# Totoro.net
KiCad netlist of a schematic drawn in EAGLE
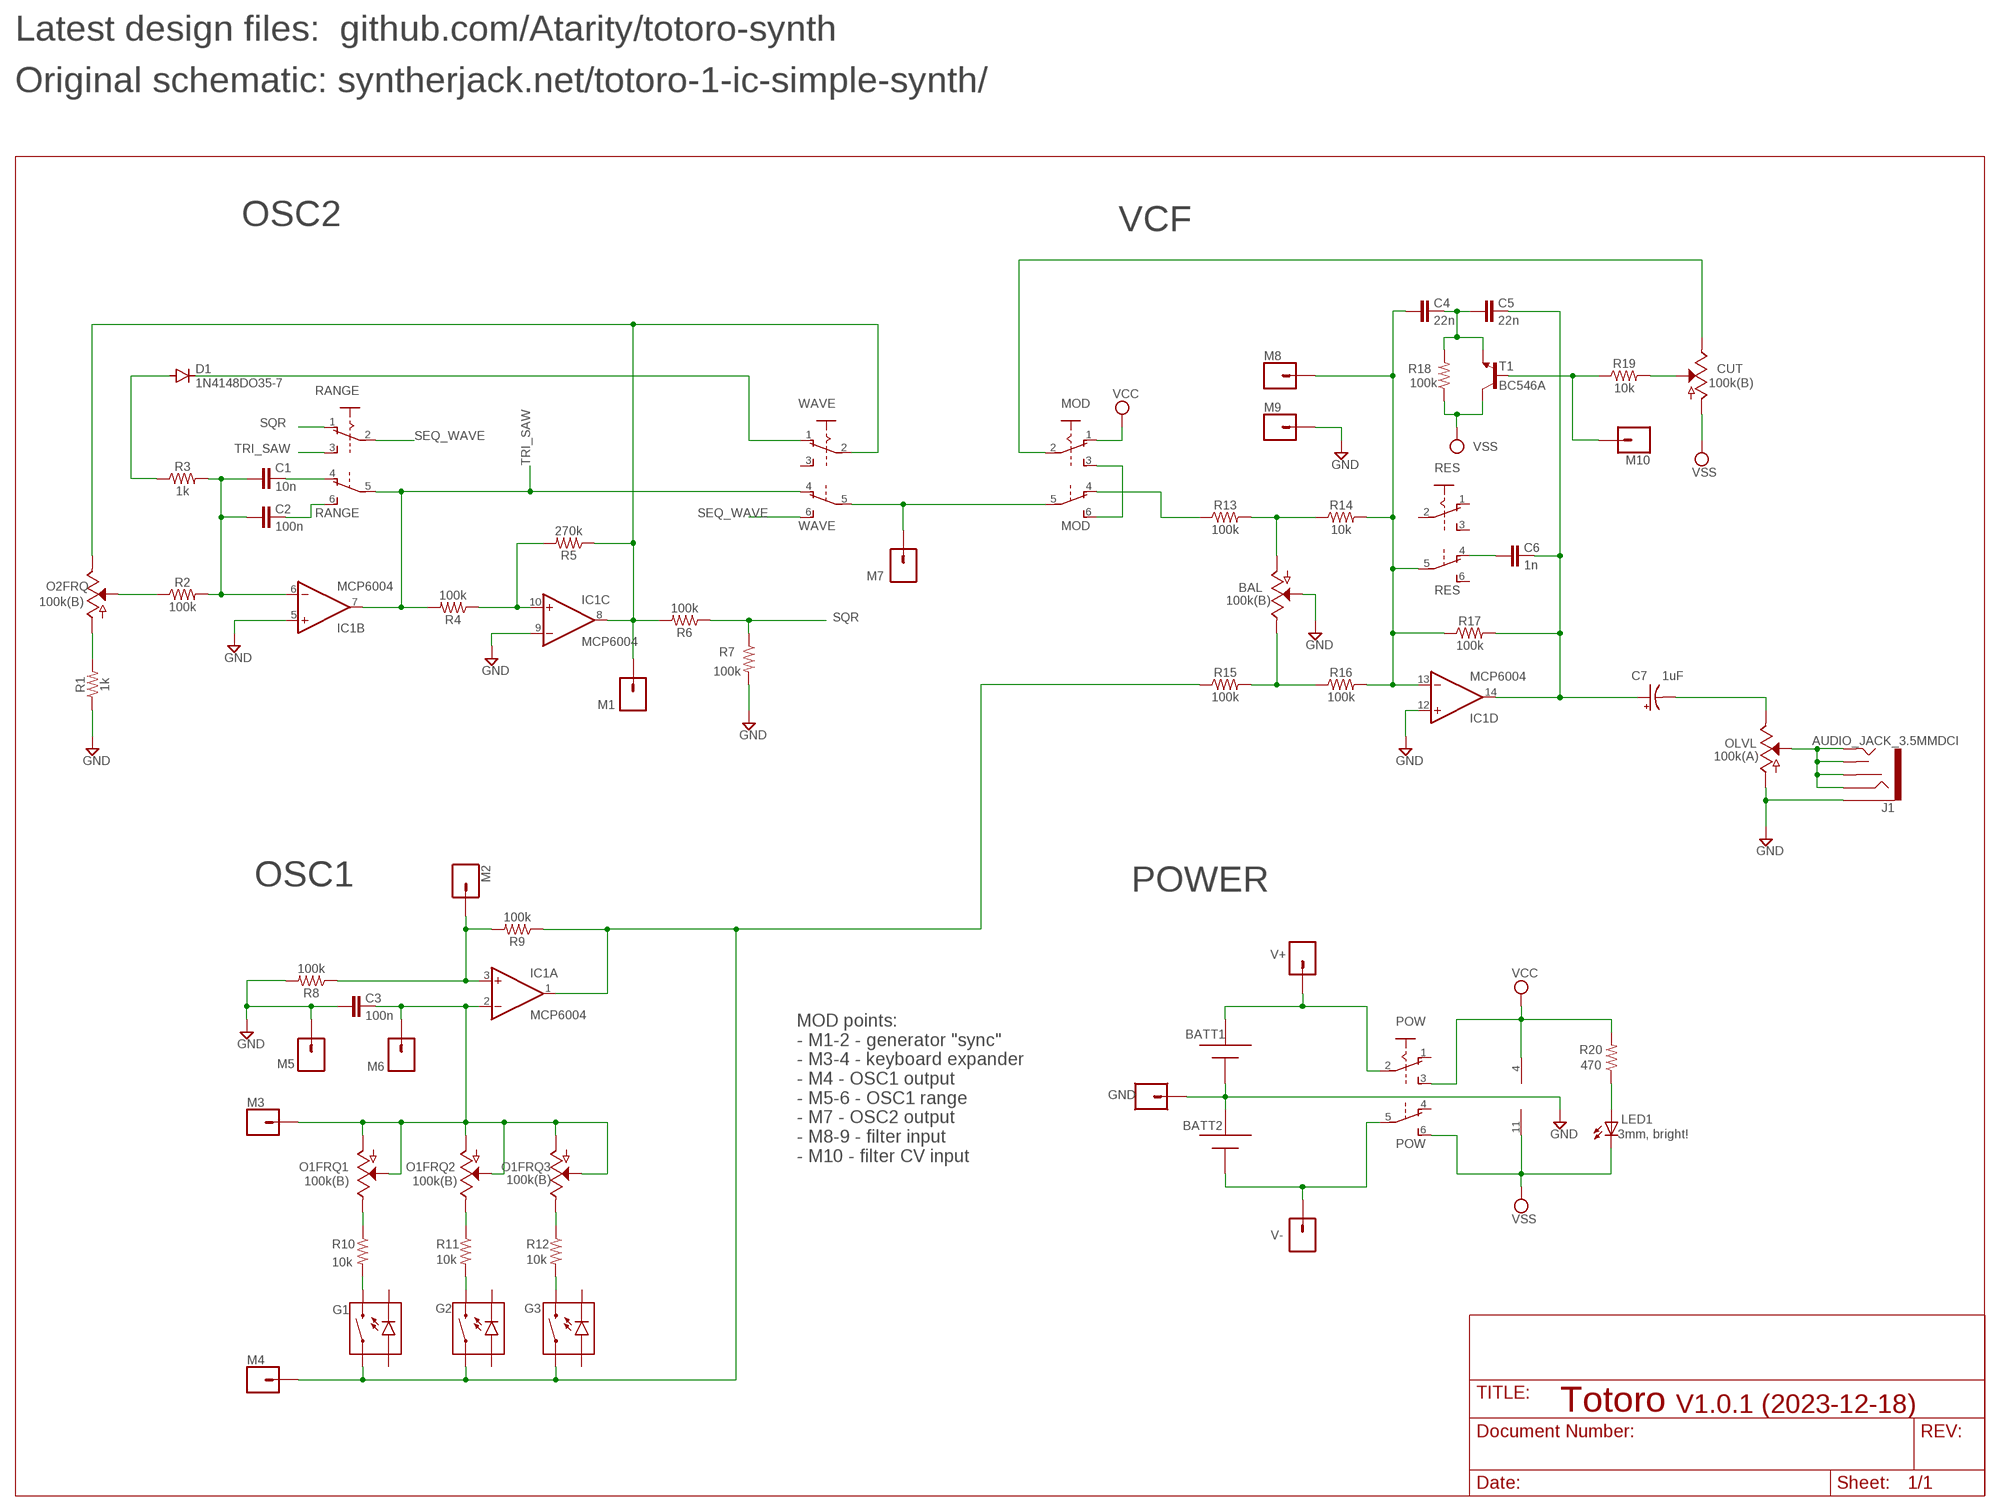
[diagram p0: schematic, sheet 1]

(export (version "E")
  (design (tool "Eeschema 10.0.6"))
  (components
    (comp (ref "BAL")
      (value "100k(B)")
      (footprint "eagle-import:POT-PTH-ALPS-KIT")
      (libsource (lib "eagle-import") (part "POTENTIOMETER-GATE-SWAPPED"))
    )
    (comp (ref "BATT1")
      (value "ATARITY-AAAKLS5-817D")
      (footprint "eagle-import:KLS5-817-D")
      (libsource (lib "eagle-import") (part "ATARITY-AAAKLS5-817D"))
    )
    (comp (ref "BATT2")
      (value "ATARITY-AAAKLS5-817D")
      (footprint "eagle-import:KLS5-817-D")
      (libsource (lib "eagle-import") (part "ATARITY-AAAKLS5-817D"))
    )
    (comp (ref "C1")
      (value "10n")
      (footprint "eagle-import:C050-024X044")
      (libsource (lib "eagle-import") (part "C-EU050-024X044"))
    )
    (comp (ref "C2")
      (value "100n")
      (footprint "eagle-import:C050-024X044")
      (libsource (lib "eagle-import") (part "C-EU050-024X044"))
    )
    (comp (ref "C3")
      (value "100n")
      (footprint "eagle-import:C050-024X044")
      (libsource (lib "eagle-import") (part "C-EU050-024X044"))
    )
    (comp (ref "C4")
      (value "22n")
      (footprint "eagle-import:C050-024X044")
      (libsource (lib "eagle-import") (part "C-EU050-024X044"))
    )
    (comp (ref "C5")
      (value "22n")
      (footprint "eagle-import:C050-024X044")
      (libsource (lib "eagle-import") (part "C-EU050-024X044"))
    )
    (comp (ref "C6")
      (value "1n")
      (footprint "eagle-import:C050-024X044")
      (libsource (lib "eagle-import") (part "C-EU050-024X044"))
    )
    (comp (ref "C7")
      (value "1uF")
      (footprint "eagle-import:CPOL-RADIAL-2.5MM-5MM")
      (libsource (lib "eagle-import") (part "10UF-POLAR-RADIAL-2.5MM-25V-20%"))
    )
    (comp (ref "CUT")
      (value "100k(B)")
      (footprint "eagle-import:POT-PTH-ALPS-KIT")
      (libsource (lib "eagle-import") (part "POTENTIOMETER-GATE-SWAPPED"))
    )
    (comp (ref "D1")
      (value "1N4148DO35-7")
      (footprint "eagle-import:DO35-7")
      (libsource (lib "eagle-import") (part "1N4148DO35-7"))
    )
    (comp (ref "G1")
      (value "MECHANICAL-KEYBOARD1U")
      (footprint "eagle-import:CHERRY-MX-LED-1U")
      (libsource (lib "eagle-import") (part "MECHANICAL-KEYBOARD1U"))
    )
    (comp (ref "G2")
      (value "MECHANICAL-KEYBOARD1U")
      (footprint "eagle-import:CHERRY-MX-LED-1U")
      (libsource (lib "eagle-import") (part "MECHANICAL-KEYBOARD1U"))
    )
    (comp (ref "G3")
      (value "MECHANICAL-KEYBOARD1U")
      (footprint "eagle-import:CHERRY-MX-LED-1U")
      (libsource (lib "eagle-import") (part "MECHANICAL-KEYBOARD1U"))
    )
    (comp (ref "GND")
      (value "CONN_01")
      (footprint "eagle-import:1X01")
      (libsource (lib "eagle-import") (part "CONN_01"))
    )
    (comp (ref "IC1")
      (value "MCP6004")
      (footprint "eagle-import:DIL14")
      (libsource (lib "eagle-import") (part "4AMP_P4+11N"))
    )
    (comp (ref "J1")
      (value "AUDIO_JACK_3.5MMDCI")
      (footprint "eagle-import:DCI-ST-033")
      (libsource (lib "eagle-import") (part "AUDIO_JACK_3.5MMDCI"))
    )
    (comp (ref "LED1")
      (value "3mm, bright!")
      (footprint "eagle-import:LED3MM")
      (libsource (lib "eagle-import") (part "LED3MM"))
    )
    (comp (ref "M1")
      (value "CONN_01")
      (footprint "eagle-import:1X01")
      (libsource (lib "eagle-import") (part "CONN_01"))
    )
    (comp (ref "M2")
      (value "CONN_01")
      (footprint "eagle-import:1X01")
      (libsource (lib "eagle-import") (part "CONN_01"))
    )
    (comp (ref "M3")
      (value "CONN_01")
      (footprint "eagle-import:1X01")
      (libsource (lib "eagle-import") (part "CONN_01"))
    )
    (comp (ref "M4")
      (value "CONN_01")
      (footprint "eagle-import:1X01")
      (libsource (lib "eagle-import") (part "CONN_01"))
    )
    (comp (ref "M5")
      (value "CONN_01")
      (footprint "eagle-import:1X01")
      (libsource (lib "eagle-import") (part "CONN_01"))
    )
    (comp (ref "M6")
      (value "CONN_01")
      (footprint "eagle-import:1X01")
      (libsource (lib "eagle-import") (part "CONN_01"))
    )
    (comp (ref "M7")
      (value "CONN_01")
      (footprint "eagle-import:1X01")
      (libsource (lib "eagle-import") (part "CONN_01"))
    )
    (comp (ref "M8")
      (value "CONN_01")
      (footprint "eagle-import:1X01")
      (libsource (lib "eagle-import") (part "CONN_01"))
    )
    (comp (ref "M9")
      (value "CONN_01")
      (footprint "eagle-import:1X01")
      (libsource (lib "eagle-import") (part "CONN_01"))
    )
    (comp (ref "M10")
      (value "CONN_01")
      (footprint "eagle-import:1X01")
      (libsource (lib "eagle-import") (part "CONN_01"))
    )
    (comp (ref "MOD")
      (value "PB22E07")
      (footprint "eagle-import:PB22E07")
      (libsource (lib "eagle-import") (part "PB22E07"))
    )
    (comp (ref "O1FRQ1")
      (value "100k(B)")
      (footprint "eagle-import:POT-PTH-ALPS-KIT")
      (libsource (lib "eagle-import") (part "POTENTIOMETER-GATE-SWAPPED"))
    )
    (comp (ref "O1FRQ2")
      (value "100k(B)")
      (footprint "eagle-import:POT-PTH-ALPS-KIT")
      (libsource (lib "eagle-import") (part "POTENTIOMETER-GATE-SWAPPED"))
    )
    (comp (ref "O1FRQ3")
      (value "100k(B)")
      (footprint "eagle-import:POT-PTH-ALPS-KIT")
      (libsource (lib "eagle-import") (part "POTENTIOMETER-GATE-SWAPPED"))
    )
    (comp (ref "O2FRQ")
      (value "100k(B)")
      (footprint "eagle-import:POT-PTH-ALPS-KIT")
      (libsource (lib "eagle-import") (part "POTENTIOMETER-GATE-SWAPPED"))
    )
    (comp (ref "OLVL")
      (value "100k(A)")
      (footprint "eagle-import:POT-PTH-ALPS-KIT")
      (libsource (lib "eagle-import") (part "POTENTIOMETER-GATE-SWAPPED"))
    )
    (comp (ref "POW")
      (value "PB22E07")
      (footprint "eagle-import:PB22E07")
      (libsource (lib "eagle-import") (part "PB22E07"))
    )
    (comp (ref "R1")
      (value "1k")
      (footprint "eagle-import:AXIAL-0.3")
      (libsource (lib "eagle-import") (part "RESISTORAXIAL-0.3"))
    )
    (comp (ref "R2")
      (value "100k")
      (footprint "eagle-import:AXIAL-0.3")
      (libsource (lib "eagle-import") (part "RESISTORAXIAL-0.3"))
    )
    (comp (ref "R3")
      (value "1k")
      (footprint "eagle-import:AXIAL-0.3")
      (libsource (lib "eagle-import") (part "RESISTORAXIAL-0.3"))
    )
    (comp (ref "R4")
      (value "100k")
      (footprint "eagle-import:AXIAL-0.3")
      (libsource (lib "eagle-import") (part "RESISTORAXIAL-0.3"))
    )
    (comp (ref "R5")
      (value "270k")
      (footprint "eagle-import:AXIAL-0.3")
      (libsource (lib "eagle-import") (part "RESISTORAXIAL-0.3"))
    )
    (comp (ref "R6")
      (value "100k")
      (footprint "eagle-import:AXIAL-0.3")
      (libsource (lib "eagle-import") (part "RESISTORAXIAL-0.3"))
    )
    (comp (ref "R7")
      (value "100k")
      (footprint "eagle-import:AXIAL-0.3")
      (libsource (lib "eagle-import") (part "RESISTORAXIAL-0.3"))
    )
    (comp (ref "R8")
      (value "100k")
      (footprint "eagle-import:AXIAL-0.3")
      (libsource (lib "eagle-import") (part "RESISTORAXIAL-0.3"))
    )
    (comp (ref "R9")
      (value "100k")
      (footprint "eagle-import:AXIAL-0.3")
      (libsource (lib "eagle-import") (part "RESISTORAXIAL-0.3"))
    )
    (comp (ref "R10")
      (value "10k")
      (footprint "eagle-import:AXIAL-0.3")
      (libsource (lib "eagle-import") (part "RESISTORAXIAL-0.3"))
    )
    (comp (ref "R11")
      (value "10k")
      (footprint "eagle-import:AXIAL-0.3")
      (libsource (lib "eagle-import") (part "RESISTORAXIAL-0.3"))
    )
    (comp (ref "R12")
      (value "10k")
      (footprint "eagle-import:AXIAL-0.3")
      (libsource (lib "eagle-import") (part "RESISTORAXIAL-0.3"))
    )
    (comp (ref "R13")
      (value "100k")
      (footprint "eagle-import:AXIAL-0.3")
      (libsource (lib "eagle-import") (part "RESISTORAXIAL-0.3"))
    )
    (comp (ref "R14")
      (value "10k")
      (footprint "eagle-import:AXIAL-0.3")
      (libsource (lib "eagle-import") (part "RESISTORAXIAL-0.3"))
    )
    (comp (ref "R15")
      (value "100k")
      (footprint "eagle-import:AXIAL-0.3")
      (libsource (lib "eagle-import") (part "RESISTORAXIAL-0.3"))
    )
    (comp (ref "R16")
      (value "100k")
      (footprint "eagle-import:AXIAL-0.3")
      (libsource (lib "eagle-import") (part "RESISTORAXIAL-0.3"))
    )
    (comp (ref "R17")
      (value "100k")
      (footprint "eagle-import:AXIAL-0.3")
      (libsource (lib "eagle-import") (part "RESISTORAXIAL-0.3"))
    )
    (comp (ref "R18")
      (value "100k")
      (footprint "eagle-import:AXIAL-0.3")
      (libsource (lib "eagle-import") (part "RESISTORAXIAL-0.3"))
    )
    (comp (ref "R19")
      (value "10k")
      (footprint "eagle-import:AXIAL-0.3")
      (libsource (lib "eagle-import") (part "RESISTORAXIAL-0.3"))
    )
    (comp (ref "R20")
      (value "470")
      (footprint "eagle-import:AXIAL-0.3")
      (libsource (lib "eagle-import") (part "RESISTORAXIAL-0.3"))
    )
    (comp (ref "RANGE")
      (value "PB22E07")
      (footprint "eagle-import:PB22E07")
      (libsource (lib "eagle-import") (part "PB22E07"))
    )
    (comp (ref "RES")
      (value "PB22E07")
      (footprint "eagle-import:PB22E07")
      (libsource (lib "eagle-import") (part "PB22E07"))
    )
    (comp (ref "T1")
      (value "BC546A")
      (footprint "eagle-import:TO92-EBC")
      (libsource (lib "eagle-import") (part "BC546A"))
    )
    (comp (ref "V+")
      (value "CONN_01")
      (footprint "eagle-import:1X01")
      (libsource (lib "eagle-import") (part "CONN_01"))
    )
    (comp (ref "V-")
      (value "CONN_01")
      (footprint "eagle-import:1X01")
      (libsource (lib "eagle-import") (part "CONN_01"))
    )
    (comp (ref "WAVE")
      (value "PB22E07")
      (footprint "eagle-import:PB22E07")
      (libsource (lib "eagle-import") (part "PB22E07"))
    )
  )
  (nets
    (net (code "1") (name "/SEQ_WAVE") (class "Default")
      (node (ref "RANGE") (pin "2") (pinfunction "P_2") (pintype "passive"))
      (node (ref "WAVE") (pin "6") (pinfunction "S_6") (pintype "passive"))
    )
    (net (code "2") (name "/SQR") (class "Default")
      (node (ref "R6") (pin "P$1") (pinfunction "1_P$1") (pintype "passive"))
      (node (ref "R7") (pin "P$1") (pinfunction "1_P$1") (pintype "passive"))
      (node (ref "RANGE") (pin "1") (pinfunction "O_1") (pintype "passive"))
    )
    (net (code "3") (name "/TRI_SAW") (class "Default")
      (node (ref "IC1") (pin "7") (pinfunction "OUT_7") (pintype "output"))
      (node (ref "R4") (pin "P$2") (pinfunction "2_P$2") (pintype "passive"))
      (node (ref "RANGE") (pin "3") (pinfunction "S_3") (pintype "passive"))
      (node (ref "RANGE") (pin "5") (pinfunction "P_5") (pintype "passive"))
      (node (ref "WAVE") (pin "4") (pinfunction "O_4") (pintype "passive"))
    )
    (net (code "4") (name "GND") (class "Default")
      (node (ref "BAL") (pin "P$2") (pinfunction "S_P$2") (pintype "passive"))
      (node (ref "BATT1") (pin "+") (pinfunction "+_+") (pintype "bidirectional"))
      (node (ref "BATT2") (pin "-") (pinfunction "-_-") (pintype "bidirectional"))
      (node (ref "C3") (pin "2") (pinfunction "2_2") (pintype "passive"))
      (node (ref "GND") (pin "1") (pinfunction "1_1") (pintype "passive"))
      (node (ref "IC1") (pin "12") (pinfunction "+IN_12") (pintype "input"))
      (node (ref "IC1") (pin "5") (pinfunction "+IN_5") (pintype "input"))
      (node (ref "IC1") (pin "9") (pinfunction "-IN_9") (pintype "input"))
      (node (ref "J1") (pin "P2") (pinfunction "SLEEVE_P2") (pintype "bidirectional"))
      (node (ref "J1") (pin "P3") (pinfunction "SLEEVE_P3") (pintype "bidirectional"))
      (node (ref "M5") (pin "1") (pinfunction "1_1") (pintype "passive"))
      (node (ref "M9") (pin "1") (pinfunction "1_1") (pintype "passive"))
      (node (ref "OLVL") (pin "P$1") (pinfunction "A_P$1") (pintype "passive"))
      (node (ref "R1") (pin "P$1") (pinfunction "1_P$1") (pintype "passive"))
      (node (ref "R7") (pin "P$2") (pinfunction "2_P$2") (pintype "passive"))
      (node (ref "R8") (pin "P$2") (pinfunction "2_P$2") (pintype "passive"))
    )
    (net (code "5") (name "Net-(BAL-A)") (class "Default")
      (node (ref "BAL") (pin "P$1") (pinfunction "A_P$1") (pintype "passive"))
      (node (ref "R13") (pin "P$2") (pinfunction "2_P$2") (pintype "passive"))
      (node (ref "R14") (pin "P$1") (pinfunction "1_P$1") (pintype "passive"))
    )
    (net (code "6") (name "Net-(BAL-E)") (class "Default")
      (node (ref "BAL") (pin "P$3") (pinfunction "E_P$3") (pintype "passive"))
      (node (ref "R15") (pin "P$2") (pinfunction "2_P$2") (pintype "passive"))
      (node (ref "R16") (pin "P$1") (pinfunction "1_P$1") (pintype "passive"))
    )
    (net (code "7") (name "Net-(C7-+)") (class "Default")
      (node (ref "C5") (pin "1") (pinfunction "1_1") (pintype "passive"))
      (node (ref "C6") (pin "1") (pinfunction "1_1") (pintype "passive"))
      (node (ref "C7") (pin "1") (pinfunction "+_1") (pintype "passive"))
      (node (ref "IC1") (pin "14") (pinfunction "OUT_14") (pintype "output"))
      (node (ref "R17") (pin "P$2") (pinfunction "2_P$2") (pintype "passive"))
    )
    (net (code "8") (name "Net-(C7--)") (class "Default")
      (node (ref "C7") (pin "2") (pinfunction "-_2") (pintype "passive"))
      (node (ref "OLVL") (pin "P$3") (pinfunction "E_P$3") (pintype "passive"))
    )
    (net (code "9") (name "Net-(CUT-E)") (class "Default")
      (node (ref "CUT") (pin "P$3") (pinfunction "E_P$3") (pintype "passive"))
      (node (ref "MOD") (pin "2") (pinfunction "P_2") (pintype "passive"))
    )
    (net (code "10") (name "Net-(CUT-S)") (class "Default")
      (node (ref "CUT") (pin "P$2") (pinfunction "S_P$2") (pintype "passive"))
      (node (ref "R19") (pin "P$2") (pinfunction "2_P$2") (pintype "passive"))
    )
    (net (code "11") (name "Net-(G1-1)") (class "Default")
      (node (ref "G1") (pin "S1") (pinfunction "1_S1") (pintype "passive"))
      (node (ref "G2") (pin "S1") (pinfunction "1_S1") (pintype "passive"))
      (node (ref "G3") (pin "S1") (pinfunction "1_S1") (pintype "passive"))
      (node (ref "IC1") (pin "1") (pinfunction "OUT_1") (pintype "output"))
      (node (ref "M4") (pin "1") (pinfunction "1_1") (pintype "passive"))
      (node (ref "R15") (pin "P$1") (pinfunction "1_P$1") (pintype "passive"))
      (node (ref "R9") (pin "P$1") (pinfunction "1_P$1") (pintype "passive"))
    )
    (net (code "12") (name "Net-(G1-2)") (class "Default")
      (node (ref "G1") (pin "S2") (pinfunction "2_S2") (pintype "passive"))
      (node (ref "R10") (pin "P$2") (pinfunction "2_P$2") (pintype "passive"))
    )
    (net (code "13") (name "Net-(G2-2)") (class "Default")
      (node (ref "G2") (pin "S2") (pinfunction "2_S2") (pintype "passive"))
      (node (ref "R11") (pin "P$2") (pinfunction "2_P$2") (pintype "passive"))
    )
    (net (code "14") (name "Net-(G3-2)") (class "Default")
      (node (ref "G3") (pin "S2") (pinfunction "2_S2") (pintype "passive"))
      (node (ref "R12") (pin "P$2") (pinfunction "2_P$2") (pintype "passive"))
    )
    (net (code "15") (name "Net-(IC1A-+IN)") (class "Default")
      (node (ref "IC1") (pin "3") (pinfunction "+IN_3") (pintype "input"))
      (node (ref "M2") (pin "1") (pinfunction "1_1") (pintype "passive"))
      (node (ref "R8") (pin "P$1") (pinfunction "1_P$1") (pintype "passive"))
      (node (ref "R9") (pin "P$2") (pinfunction "2_P$2") (pintype "passive"))
    )
    (net (code "16") (name "Net-(IC1A--IN)") (class "Default")
      (node (ref "C3") (pin "1") (pinfunction "1_1") (pintype "passive"))
      (node (ref "IC1") (pin "2") (pinfunction "-IN_2") (pintype "input"))
      (node (ref "M3") (pin "1") (pinfunction "1_1") (pintype "passive"))
      (node (ref "M6") (pin "1") (pinfunction "1_1") (pintype "passive"))
      (node (ref "O1FRQ1") (pin "P$1") (pinfunction "A_P$1") (pintype "passive"))
      (node (ref "O1FRQ1") (pin "P$2") (pinfunction "S_P$2") (pintype "passive"))
      (node (ref "O1FRQ2") (pin "P$1") (pinfunction "A_P$1") (pintype "passive"))
      (node (ref "O1FRQ2") (pin "P$2") (pinfunction "S_P$2") (pintype "passive"))
      (node (ref "O1FRQ3") (pin "P$1") (pinfunction "A_P$1") (pintype "passive"))
      (node (ref "O1FRQ3") (pin "P$2") (pinfunction "S_P$2") (pintype "passive"))
    )
    (net (code "17") (name "Net-(IC1B--IN)") (class "Default")
      (node (ref "C1") (pin "2") (pinfunction "2_2") (pintype "passive"))
      (node (ref "C2") (pin "2") (pinfunction "2_2") (pintype "passive"))
      (node (ref "IC1") (pin "6") (pinfunction "-IN_6") (pintype "input"))
      (node (ref "R2") (pin "P$2") (pinfunction "2_P$2") (pintype "passive"))
      (node (ref "R3") (pin "P$2") (pinfunction "2_P$2") (pintype "passive"))
    )
    (net (code "18") (name "Net-(IC1C-+IN)") (class "Default")
      (node (ref "IC1") (pin "10") (pinfunction "+IN_10") (pintype "input"))
      (node (ref "R4") (pin "P$1") (pinfunction "1_P$1") (pintype "passive"))
      (node (ref "R5") (pin "P$2") (pinfunction "2_P$2") (pintype "passive"))
    )
    (net (code "19") (name "Net-(IC1C-OUT)") (class "Default")
      (node (ref "IC1") (pin "8") (pinfunction "OUT_8") (pintype "output"))
      (node (ref "M1") (pin "1") (pinfunction "1_1") (pintype "passive"))
      (node (ref "O2FRQ") (pin "P$3") (pinfunction "E_P$3") (pintype "passive"))
      (node (ref "R5") (pin "P$1") (pinfunction "1_P$1") (pintype "passive"))
      (node (ref "R6") (pin "P$2") (pinfunction "2_P$2") (pintype "passive"))
      (node (ref "WAVE") (pin "2") (pinfunction "P_2") (pintype "passive"))
    )
    (net (code "20") (name "Net-(IC1D--IN)") (class "Default")
      (node (ref "C4") (pin "2") (pinfunction "2_2") (pintype "passive"))
      (node (ref "IC1") (pin "13") (pinfunction "-IN_13") (pintype "input"))
      (node (ref "M8") (pin "1") (pinfunction "1_1") (pintype "passive"))
      (node (ref "R14") (pin "P$2") (pinfunction "2_P$2") (pintype "passive"))
      (node (ref "R16") (pin "P$2") (pinfunction "2_P$2") (pintype "passive"))
      (node (ref "R17") (pin "P$1") (pinfunction "1_P$1") (pintype "passive"))
      (node (ref "RES") (pin "5") (pinfunction "P_5") (pintype "passive"))
    )
    (net (code "21") (name "Net-(J1-RING)") (class "Default")
      (node (ref "J1") (pin "P0") (pinfunction "TIP_P0") (pintype "bidirectional"))
      (node (ref "J1") (pin "P1") (pinfunction "RING_P1") (pintype "bidirectional"))
      (node (ref "J1") (pin "P4") (pinfunction "RSH_P4") (pintype "bidirectional"))
      (node (ref "J1") (pin "P5") (pinfunction "TSH_P5") (pintype "bidirectional"))
      (node (ref "OLVL") (pin "P$2") (pinfunction "S_P$2") (pintype "passive"))
    )
    (net (code "22") (name "Net-(MODA-S)") (class "Default")
      (node (ref "MOD") (pin "3") (pinfunction "S_3") (pintype "passive"))
      (node (ref "MOD") (pin "6") (pinfunction "S_6") (pintype "passive"))
    )
    (net (code "23") (name "Net-(MODB-O)") (class "Default")
      (node (ref "MOD") (pin "4") (pinfunction "O_4") (pintype "passive"))
      (node (ref "R13") (pin "P$1") (pinfunction "1_P$1") (pintype "passive"))
    )
    (net (code "24") (name "Net-(MODB-P)") (class "Default")
      (node (ref "M7") (pin "1") (pinfunction "1_1") (pintype "passive"))
      (node (ref "MOD") (pin "5") (pinfunction "P_5") (pintype "passive"))
      (node (ref "WAVE") (pin "5") (pinfunction "P_5") (pintype "passive"))
    )
    (net (code "25") (name "Net-(O1FRQ1-E)") (class "Default")
      (node (ref "O1FRQ1") (pin "P$3") (pinfunction "E_P$3") (pintype "passive"))
      (node (ref "R10") (pin "P$1") (pinfunction "1_P$1") (pintype "passive"))
    )
    (net (code "26") (name "Net-(O1FRQ2-E)") (class "Default")
      (node (ref "O1FRQ2") (pin "P$3") (pinfunction "E_P$3") (pintype "passive"))
      (node (ref "R11") (pin "P$1") (pinfunction "1_P$1") (pintype "passive"))
    )
    (net (code "27") (name "Net-(O1FRQ3-E)") (class "Default")
      (node (ref "O1FRQ3") (pin "P$3") (pinfunction "E_P$3") (pintype "passive"))
      (node (ref "R12") (pin "P$1") (pinfunction "1_P$1") (pintype "passive"))
    )
    (net (code "28") (name "Net-(O2FRQ-A)") (class "Default")
      (node (ref "O2FRQ") (pin "P$1") (pinfunction "A_P$1") (pintype "passive"))
      (node (ref "R1") (pin "P$2") (pinfunction "2_P$2") (pintype "passive"))
    )
    (net (code "29") (name "Net-(O2FRQ-S)") (class "Default")
      (node (ref "O2FRQ") (pin "P$2") (pinfunction "S_P$2") (pintype "passive"))
      (node (ref "R2") (pin "P$1") (pinfunction "1_P$1") (pintype "passive"))
    )
    (net (code "30") (name "Net-(POWA-P)") (class "Default")
      (node (ref "BATT1") (pin "-") (pinfunction "-_-") (pintype "bidirectional"))
      (node (ref "POW") (pin "2") (pinfunction "P_2") (pintype "passive"))
      (node (ref "V+") (pin "1") (pinfunction "1_1") (pintype "passive"))
    )
    (net (code "31") (name "Net-(POWB-P)") (class "Default")
      (node (ref "BATT2") (pin "+") (pinfunction "+_+") (pintype "bidirectional"))
      (node (ref "POW") (pin "5") (pinfunction "P_5") (pintype "passive"))
      (node (ref "V-") (pin "1") (pinfunction "1_1") (pintype "passive"))
    )
    (net (code "32") (name "Net-(R3-1)") (class "Default")
      (node (ref "D1") (pin "A") (pinfunction "A_A") (pintype "passive"))
      (node (ref "R3") (pin "P$1") (pinfunction "1_P$1") (pintype "passive"))
    )
    (net (code "33") (name "Net-(R18-2)") (class "Default")
      (node (ref "C4") (pin "1") (pinfunction "1_1") (pintype "passive"))
      (node (ref "C5") (pin "2") (pinfunction "2_2") (pintype "passive"))
      (node (ref "R18") (pin "P$2") (pinfunction "2_P$2") (pintype "passive"))
      (node (ref "T1") (pin "E") (pinfunction "E_E") (pintype "passive"))
    )
    (net (code "34") (name "Net-(R19-1)") (class "Default")
      (node (ref "M10") (pin "1") (pinfunction "1_1") (pintype "passive"))
      (node (ref "R19") (pin "P$1") (pinfunction "1_P$1") (pintype "passive"))
      (node (ref "T1") (pin "B") (pinfunction "B_B") (pintype "passive"))
    )
    (net (code "35") (name "Net-(R20-1)") (class "Default")
      (node (ref "LED1") (pin "A") (pinfunction "A_A") (pintype "passive"))
      (node (ref "R20") (pin "P$1") (pinfunction "1_P$1") (pintype "passive"))
    )
    (net (code "36") (name "Net-(RANGEB-O)") (class "Default")
      (node (ref "C1") (pin "1") (pinfunction "1_1") (pintype "passive"))
      (node (ref "RANGE") (pin "4") (pinfunction "O_4") (pintype "passive"))
    )
    (net (code "37") (name "Net-(RANGEB-S)") (class "Default")
      (node (ref "C2") (pin "1") (pinfunction "1_1") (pintype "passive"))
      (node (ref "RANGE") (pin "6") (pinfunction "S_6") (pintype "passive"))
    )
    (net (code "38") (name "Net-(RESB-O)") (class "Default")
      (node (ref "C6") (pin "2") (pinfunction "2_2") (pintype "passive"))
      (node (ref "RES") (pin "4") (pinfunction "O_4") (pintype "passive"))
    )
    (net (code "39") (name "Net-(WAVEA-O)") (class "Default")
      (node (ref "D1") (pin "C") (pinfunction "C_C") (pintype "passive"))
      (node (ref "WAVE") (pin "1") (pinfunction "O_1") (pintype "passive"))
    )
    (net (code "40") (name "VCC") (class "Default")
      (node (ref "IC1") (pin "4") (pinfunction "V+_4") (pintype "power_in"))
      (node (ref "MOD") (pin "1") (pinfunction "O_1") (pintype "passive"))
      (node (ref "POW") (pin "3") (pinfunction "S_3") (pintype "passive"))
      (node (ref "R20") (pin "P$2") (pinfunction "2_P$2") (pintype "passive"))
    )
    (net (code "41") (name "VSS") (class "Default")
      (node (ref "CUT") (pin "P$1") (pinfunction "A_P$1") (pintype "passive"))
      (node (ref "IC1") (pin "11") (pinfunction "V-_11") (pintype "power_in"))
      (node (ref "LED1") (pin "K") (pinfunction "C_K") (pintype "passive"))
      (node (ref "POW") (pin "6") (pinfunction "S_6") (pintype "passive"))
      (node (ref "R18") (pin "P$1") (pinfunction "1_P$1") (pintype "passive"))
      (node (ref "T1") (pin "C") (pinfunction "C_C") (pintype "passive"))
    )
    (net (code "42") (name "unconnected-(G1-C-PadK)") (class "Default")
      (node (ref "G1") (pin "K") (pinfunction "C_K") (pintype "passive"))
    )
    (net (code "43") (name "unconnected-(G1-PadA)") (class "Default")
      (node (ref "G1") (pin "A") (pinfunction "A_A") (pintype "passive"))
    )
    (net (code "44") (name "unconnected-(G2-C-PadK)") (class "Default")
      (node (ref "G2") (pin "K") (pinfunction "C_K") (pintype "passive"))
    )
    (net (code "45") (name "unconnected-(G2-PadA)") (class "Default")
      (node (ref "G2") (pin "A") (pinfunction "A_A") (pintype "passive"))
    )
    (net (code "46") (name "unconnected-(G3-C-PadK)") (class "Default")
      (node (ref "G3") (pin "K") (pinfunction "C_K") (pintype "passive"))
    )
    (net (code "47") (name "unconnected-(G3-PadA)") (class "Default")
      (node (ref "G3") (pin "A") (pinfunction "A_A") (pintype "passive"))
    )
    (net (code "48") (name "unconnected-(POWA-O-Pad1)") (class "Default")
      (node (ref "POW") (pin "1") (pinfunction "O_1") (pintype "passive"))
    )
    (net (code "49") (name "unconnected-(POWB-O-Pad4)") (class "Default")
      (node (ref "POW") (pin "4") (pinfunction "O_4") (pintype "passive"))
    )
    (net (code "50") (name "unconnected-(RESA-O-Pad1)") (class "Default")
      (node (ref "RES") (pin "1") (pinfunction "O_1") (pintype "passive"))
    )
    (net (code "51") (name "unconnected-(RESA-P-Pad2)") (class "Default")
      (node (ref "RES") (pin "2") (pinfunction "P_2") (pintype "passive"))
    )
    (net (code "52") (name "unconnected-(RESA-S-Pad3)") (class "Default")
      (node (ref "RES") (pin "3") (pinfunction "S_3") (pintype "passive"))
    )
    (net (code "53") (name "unconnected-(RESB-S-Pad6)") (class "Default")
      (node (ref "RES") (pin "6") (pinfunction "S_6") (pintype "passive"))
    )
    (net (code "54") (name "unconnected-(WAVEA-S-Pad3)") (class "Default")
      (node (ref "WAVE") (pin "3") (pinfunction "S_3") (pintype "passive"))
    )
  )
)
